# 03_LTC6820.net
KiCad netlist of a schematic drawn in Altium Designer
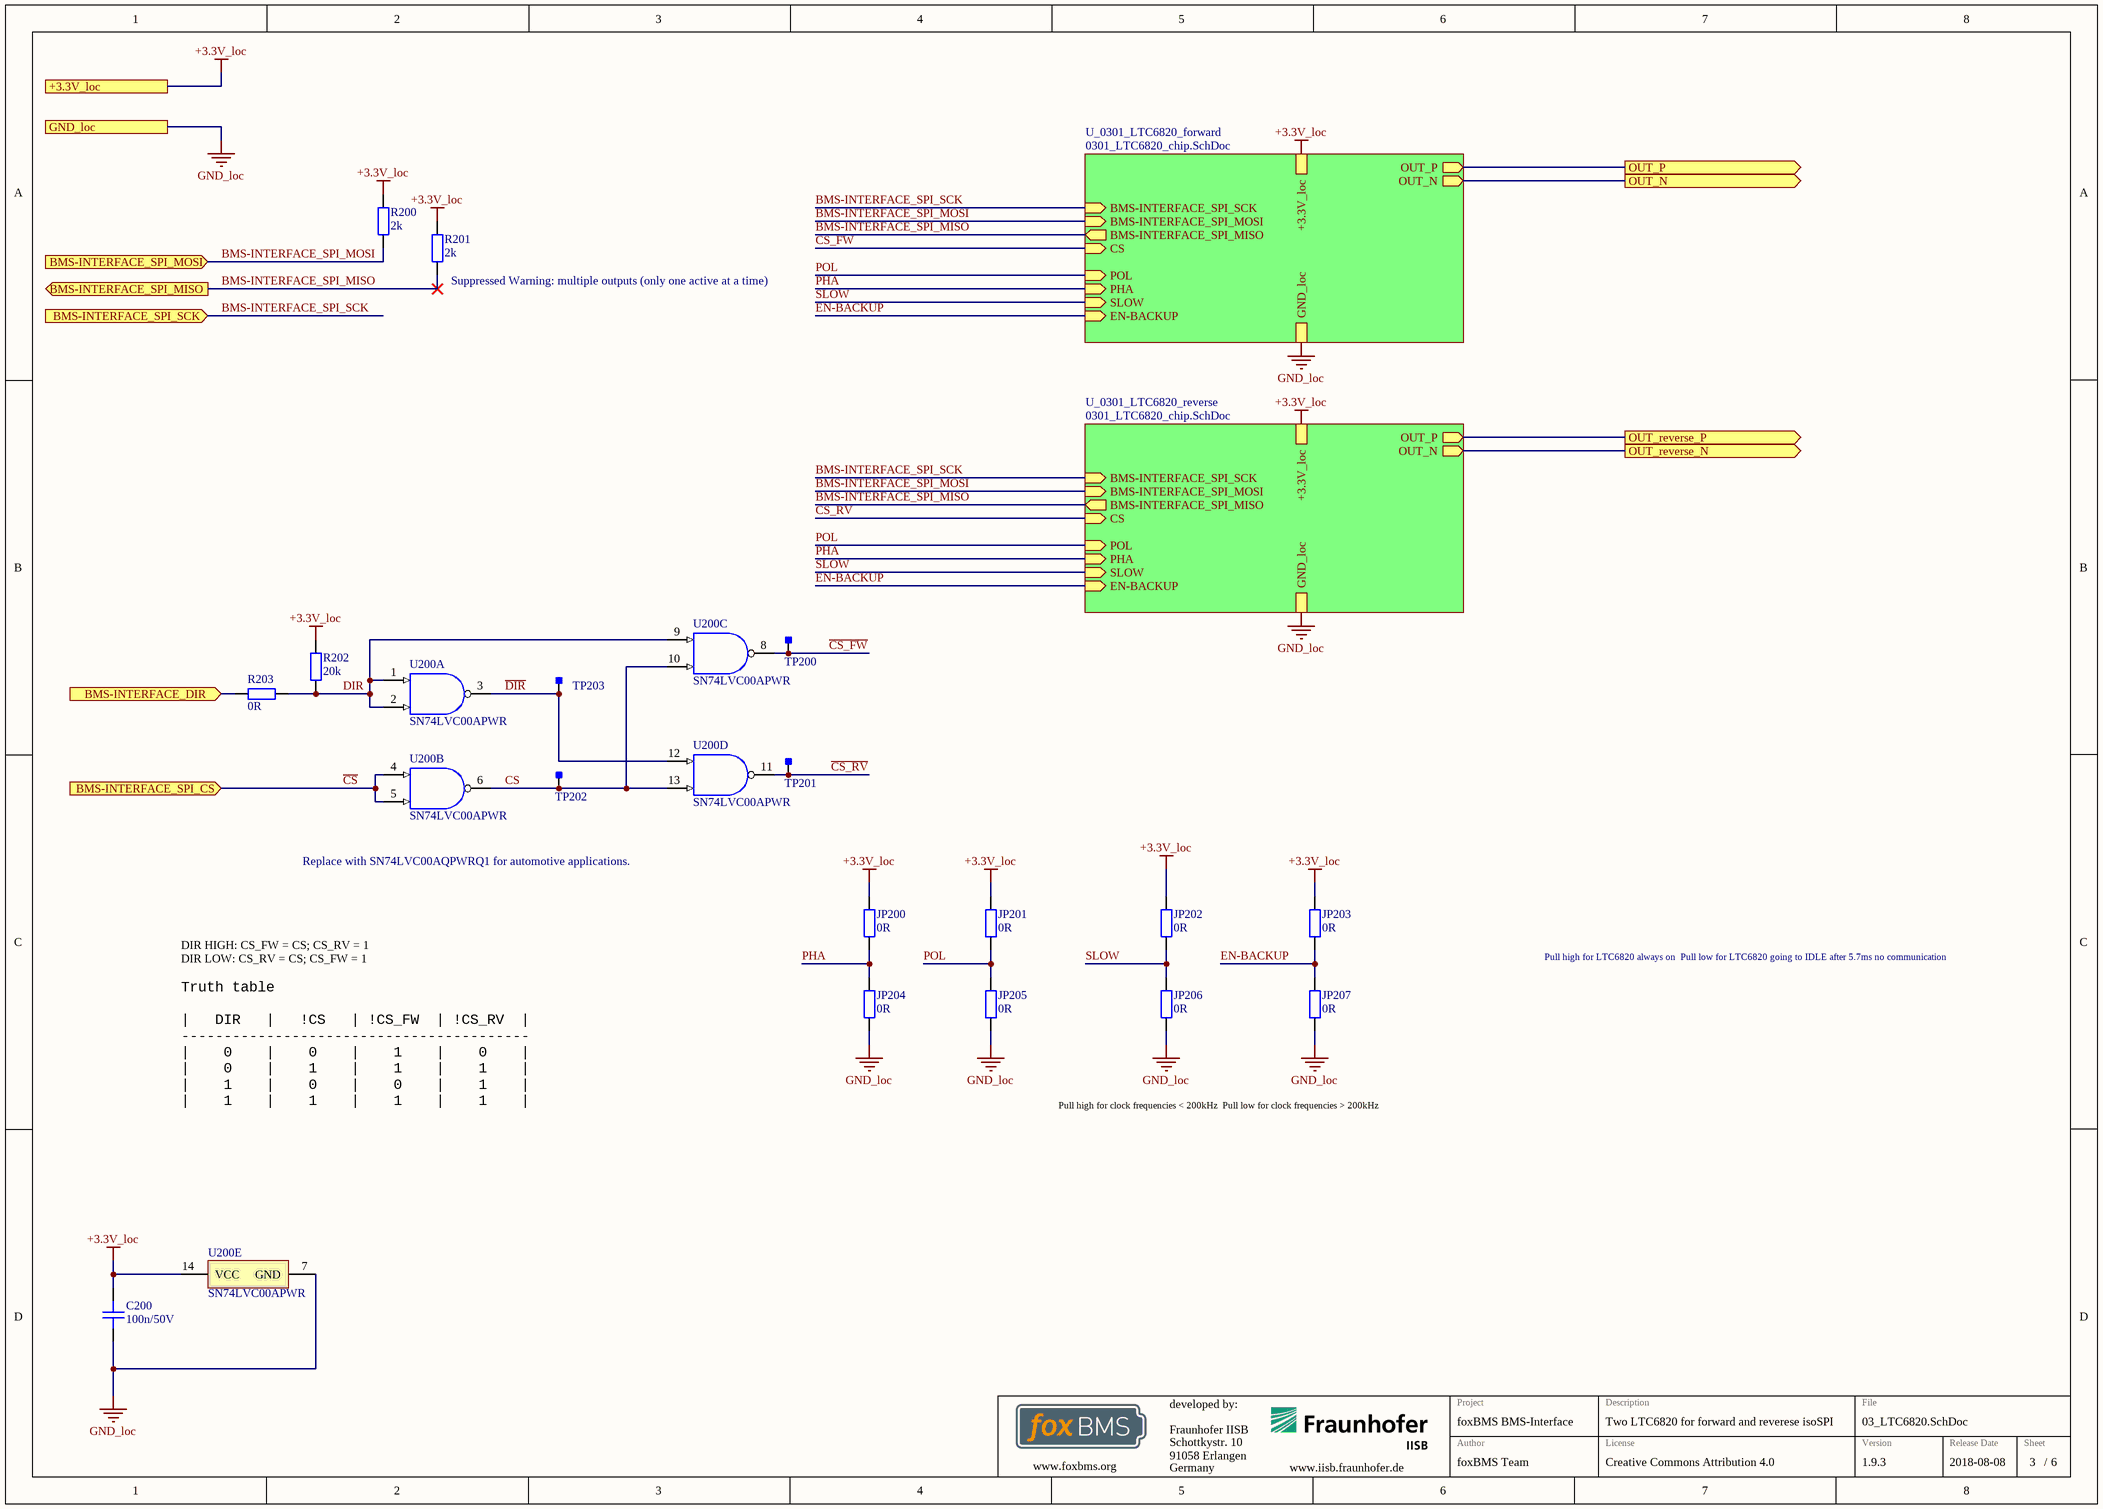
[diagram p0: 03_LTC6820.SchDoc]

(export (version "E")
  (design (tool "Eeschema 10.0.6"))
  (components
    (comp (ref "C200")
      (value "100n/50V")
      (footprint "CAPC1608X08N")
      (description "MLCC")
      (fields (field (name "PART NUMBER") "gen_C_ceramic_100n_50V_X7R_0603"))
      (libsource (lib "OE750") (part "C"))
    )
    (comp (ref "JP200")
      (value "0R")
      (footprint "RESC1608X05N")
      (description "SMD Resistor 0R 0603")
      (fields (field (name "PART NUMBER") "gen_R_0R_0603") (field (name "POWER") "0.1W"))
      (libsource (lib "OE750") (part "R"))
    )
    (comp (ref "JP201")
      (value "0R")
      (footprint "RESC1608X05N")
      (description "SMD Resistor 0R 0603")
      (fields (field (name "PART NUMBER") "gen_R_0R_0603") (field (name "POWER") "0.1W"))
      (libsource (lib "OE750") (part "R"))
    )
    (comp (ref "JP202")
      (value "0R")
      (footprint "RESC1608X05N")
      (description "SMD Resistor 0R 0603")
      (fields (field (name "PART NUMBER") "gen_R_0R_0603") (field (name "POWER") "0.1W"))
      (libsource (lib "OE750") (part "R"))
    )
    (comp (ref "JP203")
      (value "0R")
      (footprint "RESC1608X05N")
      (description "SMD Resistor 0R 0603")
      (fields (field (name "PART NUMBER") "gen_R_0R_0603") (field (name "POWER") "0.1W"))
      (libsource (lib "OE750") (part "R"))
    )
    (comp (ref "JP204")
      (value "0R")
      (footprint "RESC1608X05N")
      (description "SMD Resistor 0R 0603")
      (fields (field (name "PART NUMBER") "gen_R_0R_0603") (field (name "POWER") "0.1W"))
      (libsource (lib "OE750") (part "R"))
    )
    (comp (ref "JP205")
      (value "0R")
      (footprint "RESC1608X05N")
      (description "SMD Resistor 0R 0603")
      (fields (field (name "PART NUMBER") "gen_R_0R_0603") (field (name "POWER") "0.1W"))
      (libsource (lib "OE750") (part "R"))
    )
    (comp (ref "JP206")
      (value "0R")
      (footprint "RESC1608X05N")
      (description "SMD Resistor 0R 0603")
      (fields (field (name "PART NUMBER") "gen_R_0R_0603") (field (name "POWER") "0.1W"))
      (libsource (lib "OE750") (part "R"))
    )
    (comp (ref "JP207")
      (value "0R")
      (footprint "RESC1608X05N")
      (description "SMD Resistor 0R 0603")
      (fields (field (name "PART NUMBER") "gen_R_0R_0603") (field (name "POWER") "0.1W"))
      (libsource (lib "OE750") (part "R"))
    )
    (comp (ref "R200")
      (value "2k")
      (footprint "RESC1608X05N")
      (description "SMD Resistor 2k 0603")
      (fields (field (name "PART NUMBER") "gen_R_2k_0603") (field (name "TOLERANCE") "1%"))
      (libsource (lib "OE750") (part "R"))
    )
    (comp (ref "R201")
      (value "2k")
      (footprint "RESC1608X05N")
      (description "SMD Resistor 2k 0603")
      (fields (field (name "PART NUMBER") "gen_R_2k_0603") (field (name "TOLERANCE") "1%"))
      (libsource (lib "OE750") (part "R"))
    )
    (comp (ref "R202")
      (value "20k")
      (footprint "RESC1608X05N")
      (description "SMD Resistor 20k 0603")
      (fields (field (name "PART NUMBER") "gen_R_20k_0603") (field (name "TOLERANCE") "1%"))
      (libsource (lib "OE750") (part "R"))
    )
    (comp (ref "R203")
      (value "0R")
      (footprint "RESC1608X05N")
      (description "SMD Resistor 0R 0603")
      (fields (field (name "PART NUMBER") "gen_R_0R_0603") (field (name "POWER") "0.1W"))
      (libsource (lib "OE750") (part "R"))
    )
    (comp (ref "TP200")
      (value "Testpoint_Square")
      (footprint "Testpoint_S1")
      (description "Testpoint, square")
      (libsource (lib "OE750") (part "Testpoint_Square"))
    )
    (comp (ref "TP201")
      (value "Testpoint_Square")
      (footprint "Testpoint_S1")
      (description "Testpoint, square")
      (libsource (lib "OE750") (part "Testpoint_Square"))
    )
    (comp (ref "TP202")
      (value "Testpoint_Square")
      (footprint "Testpoint_S1")
      (description "Testpoint, square")
      (libsource (lib "OE750") (part "Testpoint_Square"))
    )
    (comp (ref "TP203")
      (value "Testpoint_Square")
      (footprint "Testpoint_S1")
      (description "Testpoint, square")
      (libsource (lib "OE750") (part "Testpoint_Square"))
    )
    (comp (ref "U200")
      (value "SN74LVC00APWR")
      (footprint "PW0014A_M")
      (description "Quadruple 2-Input Positive-NAND Gate, PW0014A, LARGE T&R")
      (fields
        (field (name "GENERIC PART NUMBER") "SN74LVC00A")
        (field (name "MANUFACTURER") "Texas Instruments")
      )
      (libsource (lib "Altium Content Vault") (part "TI-SN74LVC00A-14"))
    )
  )
  (nets
    (net (code "1") (name "+3.3V_loc") (class "Default")
      (node (ref "C200") (pin "2") (pinfunction "2_2") (pintype "passive"))
      (node (ref "JP200") (pin "2") (pinfunction "2_2") (pintype "passive"))
      (node (ref "JP201") (pin "2") (pinfunction "2_2") (pintype "passive"))
      (node (ref "JP202") (pin "2") (pinfunction "2_2") (pintype "passive"))
      (node (ref "JP203") (pin "2") (pinfunction "2_2") (pintype "passive"))
      (node (ref "R200") (pin "2") (pinfunction "2_2") (pintype "passive"))
      (node (ref "R201") (pin "2") (pinfunction "2_2") (pintype "passive"))
      (node (ref "R202") (pin "2") (pinfunction "2_2") (pintype "passive"))
      (node (ref "U200") (pin "14") (pinfunction "VCC_14") (pintype "power_in"))
    )
    (net (code "2") (name "/BMS-INTERFACE_DIR") (class "Default")
      (node (ref "R203") (pin "1") (pinfunction "1_1") (pintype "passive"))
    )
    (net (code "3") (name "/BMS-INTERFACE_SPI_MISO") (class "Default")
      (node (ref "R201") (pin "1") (pinfunction "1_1") (pintype "passive+no_connect"))
    )
    (net (code "4") (name "/BMS-INTERFACE_SPI_MOSI") (class "Default")
      (node (ref "R200") (pin "1") (pinfunction "1_1") (pintype "passive"))
    )
    (net (code "6") (name "/CS") (class "Default")
      (node (ref "TP202") (pin "1") (pinfunction "1_1") (pintype "passive"))
      (node (ref "U200") (pin "10") (pinfunction "3B_10") (pintype "input"))
      (node (ref "U200") (pin "13") (pinfunction "4B_13") (pintype "input"))
      (node (ref "U200") (pin "6") (pinfunction "2Y_6") (pintype "open_collector"))
    )
    (net (code "7") (name "/DIR") (class "Default")
      (node (ref "R202") (pin "1") (pinfunction "1_1") (pintype "passive"))
      (node (ref "R203") (pin "2") (pinfunction "2_2") (pintype "passive"))
      (node (ref "U200") (pin "1") (pinfunction "1A_1") (pintype "input"))
      (node (ref "U200") (pin "2") (pinfunction "1B_2") (pintype "input"))
      (node (ref "U200") (pin "9") (pinfunction "3A_9") (pintype "input"))
    )
    (net (code "8") (name "/EN-BACKUP") (class "Default")
      (node (ref "JP203") (pin "1") (pinfunction "1_1") (pintype "passive"))
      (node (ref "JP207") (pin "2") (pinfunction "2_2") (pintype "passive"))
    )
    (net (code "13") (name "/PHA") (class "Default")
      (node (ref "JP200") (pin "1") (pinfunction "1_1") (pintype "passive"))
      (node (ref "JP204") (pin "2") (pinfunction "2_2") (pintype "passive"))
    )
    (net (code "14") (name "/POL") (class "Default")
      (node (ref "JP201") (pin "1") (pinfunction "1_1") (pintype "passive"))
      (node (ref "JP205") (pin "2") (pinfunction "2_2") (pintype "passive"))
    )
    (net (code "15") (name "/SLOW") (class "Default")
      (node (ref "JP202") (pin "1") (pinfunction "1_1") (pintype "passive"))
      (node (ref "JP206") (pin "2") (pinfunction "2_2") (pintype "passive"))
    )
    (net (code "16") (name "/~{CS_FW}") (class "Default")
      (node (ref "TP200") (pin "1") (pinfunction "1_1") (pintype "passive"))
      (node (ref "U200") (pin "8") (pinfunction "3Y_8") (pintype "open_collector"))
    )
    (net (code "17") (name "/~{CS_RV}") (class "Default")
      (node (ref "TP201") (pin "1") (pinfunction "1_1") (pintype "passive"))
      (node (ref "U200") (pin "11") (pinfunction "4Y_11") (pintype "open_collector"))
    )
    (net (code "18") (name "/~{CS}") (class "Default")
      (node (ref "U200") (pin "4") (pinfunction "2A_4") (pintype "input"))
      (node (ref "U200") (pin "5") (pinfunction "2B_5") (pintype "input"))
    )
    (net (code "19") (name "/~{DIR}") (class "Default")
      (node (ref "TP203") (pin "1") (pinfunction "1_1") (pintype "passive"))
      (node (ref "U200") (pin "12") (pinfunction "4A_12") (pintype "input"))
      (node (ref "U200") (pin "3") (pinfunction "1Y_3") (pintype "open_collector"))
    )
    (net (code "20") (name "GND_loc") (class "Default")
      (node (ref "C200") (pin "1") (pinfunction "1_1") (pintype "passive"))
      (node (ref "JP204") (pin "1") (pinfunction "1_1") (pintype "passive"))
      (node (ref "JP205") (pin "1") (pinfunction "1_1") (pintype "passive"))
      (node (ref "JP206") (pin "1") (pinfunction "1_1") (pintype "passive"))
      (node (ref "JP207") (pin "1") (pinfunction "1_1") (pintype "passive"))
      (node (ref "U200") (pin "7") (pinfunction "GND_7") (pintype "power_in"))
    )
  )
)
